# NFC_Card3.net
KiCad netlist of a schematic drawn in EasyEDA Pro
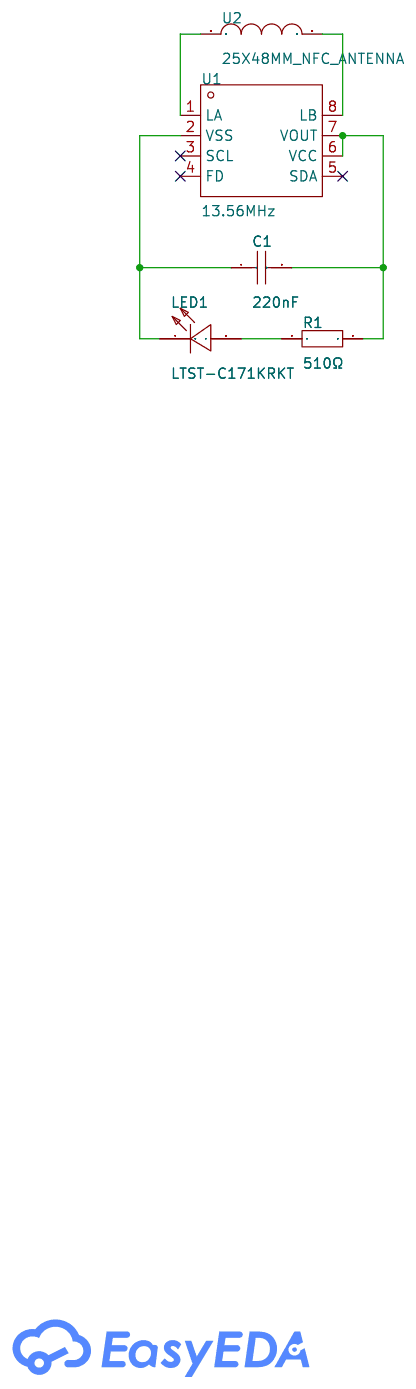
[diagram p0: schematic sheet]

(export (version "E")
  (design (tool "Eeschema 10.0.6"))
  (components
    (comp (ref "C1")
      (value "220nF")
      (footprint "easyedapro:C0603")
      (description "容值:220nF;精度:±10%;额定电压:25V;材质(温度系数):X7R;")
      (fields
        (field (name "Manufacturer Part") "CL10B224KA8NNNC")
        (field (name "Manufacturer") "SAMSUNG(三星)")
      )
      (libsource (lib "easyedapro") (part "CL10B224KA8NNNC"))
    )
    (comp (ref "LED1")
      (value "LTST-C171KRKT")
      (footprint "easyedapro:LED-SMD_L2.0-W1.25-RD_RED")
      (fields (field (name "Manufacturer") "LITEON(光宝)"))
      (libsource (lib "easyedapro") (part "LTST-C171KRKT"))
    )
    (comp (ref "R1")
      (value "510Ω")
      (footprint "easyedapro:R0402")
      (fields (field (name "Manufacturer Part") "RC0402FR-07510RL") (field (name "Manufacturer") "YAGEO(国巨)"))
      (libsource (lib "easyedapro") (part "RC0402FR-07510RL"))
    )
    (comp (ref "U1")
      (value "13.56MHz")
      (footprint "easyedapro:XQFN-8_L1.6-W1.6-P0.50-BL_NT3H2111W0FHKH")
      (fields (field (name "Manufacturer Part") "NT3H2111W0FHKH") (field (name "Manufacturer") "NXP(恩智浦)"))
      (libsource (lib "easyedapro") (part "NT3H2111W0FHKH"))
    )
    (comp (ref "U2")
      (value "25X48MM_NFC_ANTENNA")
      (footprint "easyedapro:25X48MM_NFC_ANTENNA")
      (libsource (lib "easyedapro") (part "25X48MM_NFC_ANTENNA"))
    )
  )
  (nets
    (net (code "1") (name "Net-(LED1-A)") (class "Default")
      (node (ref "LED1") (pin "2") (pinfunction "A_2") (pintype "input"))
      (node (ref "R1") (pin "1") (pinfunction "1_1") (pintype "unspecified"))
    )
    (net (code "2") (name "Net-(LED1-C)") (class "Default")
      (node (ref "C1") (pin "1") (pinfunction "1_1") (pintype "input"))
      (node (ref "LED1") (pin "1") (pinfunction "C_1") (pintype "input"))
      (node (ref "U1") (pin "2") (pinfunction "VSS_2") (pintype "unspecified"))
    )
    (net (code "3") (name "Net-(U1-LA)") (class "Default")
      (node (ref "U1") (pin "1") (pinfunction "LA_1") (pintype "unspecified"))
      (node (ref "U2") (pin "P$1") (pinfunction "P$1_P$1") (pintype "bidirectional"))
    )
    (net (code "4") (name "Net-(U1-LB)") (class "Default")
      (node (ref "U1") (pin "8") (pinfunction "LB_8") (pintype "unspecified"))
      (node (ref "U2") (pin "P$2") (pinfunction "P$2_P$2") (pintype "bidirectional"))
    )
    (net (code "5") (name "Net-(U1-VCC)") (class "Default")
      (node (ref "C1") (pin "2") (pinfunction "2_2") (pintype "input"))
      (node (ref "R1") (pin "2") (pinfunction "2_2") (pintype "unspecified"))
      (node (ref "U1") (pin "6") (pinfunction "VCC_6") (pintype "unspecified"))
      (node (ref "U1") (pin "7") (pinfunction "VOUT_7") (pintype "unspecified"))
    )
    (net (code "6") (name "unconnected-(U1-FD-Pad4)") (class "Default")
      (node (ref "U1") (pin "4") (pinfunction "FD_4") (pintype "unspecified+no_connect"))
    )
    (net (code "7") (name "unconnected-(U1-SCL-Pad3)") (class "Default")
      (node (ref "U1") (pin "3") (pinfunction "SCL_3") (pintype "unspecified+no_connect"))
    )
    (net (code "8") (name "unconnected-(U1-SDA-Pad5)") (class "Default")
      (node (ref "U1") (pin "5") (pinfunction "SDA_5") (pintype "unspecified+no_connect"))
    )
  )
)
